# Display-KeyboardModule.net
KiCad netlist of a schematic drawn in EAGLE
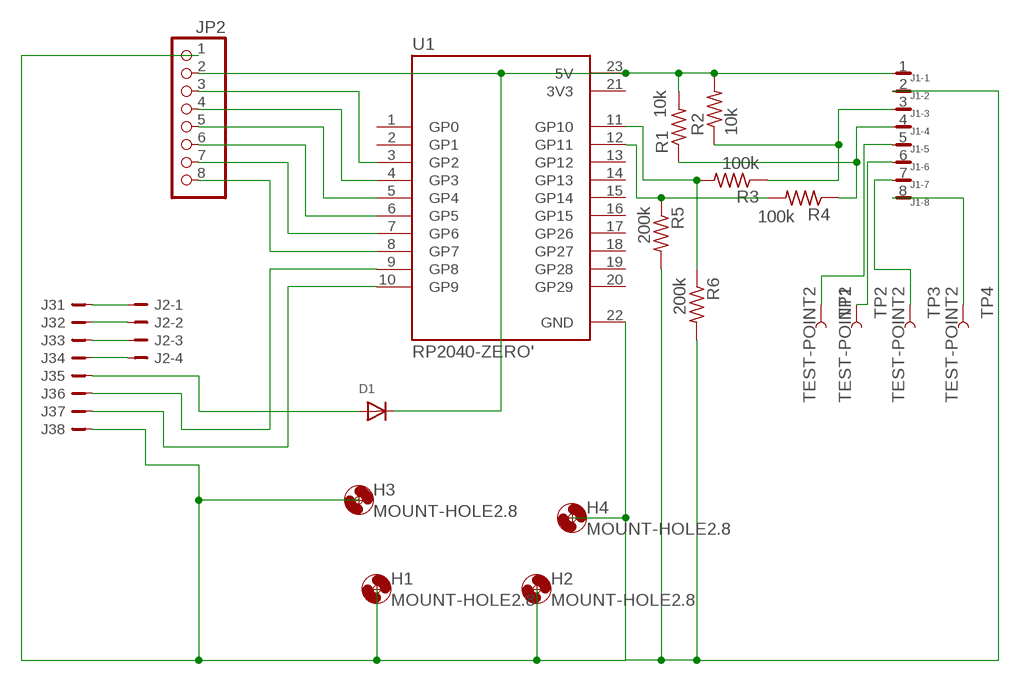
[diagram p0: schematic, sheet 1]

(export (version "E")
  (design (tool "Eeschema 10.0.6"))
  (components
    (comp (ref "D1")
      (value "DIODESMA")
      (footprint "eagle-import:SMADIODE")
      (libsource (lib "eagle-import") (part "DIODESMA"))
    )
    (comp (ref "H1")
      (value "MOUNT-HOLE2.8")
      (footprint "eagle-import:2,8")
      (libsource (lib "eagle-import") (part "MOUNT-HOLE2.8"))
    )
    (comp (ref "H2")
      (value "MOUNT-HOLE2.8")
      (footprint "eagle-import:2,8")
      (libsource (lib "eagle-import") (part "MOUNT-HOLE2.8"))
    )
    (comp (ref "H3")
      (value "MOUNT-HOLE2.8")
      (footprint "eagle-import:2,8")
      (libsource (lib "eagle-import") (part "MOUNT-HOLE2.8"))
    )
    (comp (ref "H4")
      (value "MOUNT-HOLE2.8")
      (footprint "eagle-import:2,8")
      (libsource (lib "eagle-import") (part "MOUNT-HOLE2.8"))
    )
    (comp (ref "J1")
      (value "JST-SH-8_RA")
      (footprint "eagle-import:SM08B-SRSS-TB")
      (fields (field (name "MF") "JST") (field (name "MPN") "SM08B-SRSS-TB"))
      (libsource (lib "eagle-import") (part "JST-SH-8_RA"))
    )
    (comp (ref "J2")
      (value "JST-PH-4_TH-RA")
      (footprint "eagle-import:S4B-PH-KL")
      (fields (field (name "MF") "JST") (field (name "MPN") "S4B-PH-KL"))
      (libsource (lib "eagle-import") (part "JST-PH-4_TH-RA"))
    )
    (comp (ref "J3")
      (value "B8B-PH-K-S")
      (footprint "eagle-import:B8B-PH-K-S")
      (libsource (lib "eagle-import") (part "B8B-PH-K-S"))
    )
    (comp (ref "JP2")
      (value "PINHD-1X8/90")
      (footprint "eagle-import:1X08_90")
      (libsource (lib "eagle-import") (part "PINHD-1X8/90"))
    )
    (comp (ref "R1")
      (value "10k")
      (footprint "eagle-import:R1206")
      (libsource (lib "eagle-import") (part "R-US_R1206"))
    )
    (comp (ref "R2")
      (value "10k")
      (footprint "eagle-import:R1206")
      (libsource (lib "eagle-import") (part "R-US_R1206"))
    )
    (comp (ref "R3")
      (value "100k")
      (footprint "eagle-import:R1206")
      (libsource (lib "eagle-import") (part "R-US_R1206"))
    )
    (comp (ref "R4")
      (value "100k")
      (footprint "eagle-import:R1206")
      (libsource (lib "eagle-import") (part "R-US_R1206"))
    )
    (comp (ref "R5")
      (value "200k")
      (footprint "eagle-import:R1206")
      (libsource (lib "eagle-import") (part "R-US_R1206"))
    )
    (comp (ref "R6")
      (value "200k")
      (footprint "eagle-import:R1206")
      (libsource (lib "eagle-import") (part "R-US_R1206"))
    )
    (comp (ref "TP1")
      (value "TEST-POINT2")
      (footprint "eagle-import:PAD.02X.02")
      (libsource (lib "eagle-import") (part "TEST-POINT2"))
    )
    (comp (ref "TP2")
      (value "TEST-POINT2")
      (footprint "eagle-import:PAD.02X.02")
      (libsource (lib "eagle-import") (part "TEST-POINT2"))
    )
    (comp (ref "TP3")
      (value "TEST-POINT2")
      (footprint "eagle-import:PAD.02X.02")
      (libsource (lib "eagle-import") (part "TEST-POINT2"))
    )
    (comp (ref "TP4")
      (value "TEST-POINT2")
      (footprint "eagle-import:PAD.02X.02")
      (libsource (lib "eagle-import") (part "TEST-POINT2"))
    )
    (comp (ref "U1")
      (value "RP2040-ZERO'")
      (footprint "eagle-import:MODULE_RP2040-ZERO")
      (fields (field (name "MF") "Waveshare Electronics") (field (name "MP") "RP2040-ZERO"))
      (libsource (lib "eagle-import") (part "RP2040-ZERO'"))
    )
  )
  (nets
    (net (code "1") (name "/3V3") (class "Default")
      (node (ref "U1") (pin "21") (pinfunction "3V3_21") (pintype "power_in"))
    )
    (net (code "2") (name "Net-(J1A-P)") (class "Default")
      (node (ref "D1") (pin "C") (pinfunction "C_C") (pintype "passive"))
      (node (ref "J1") (pin "1") (pinfunction "P_1") (pintype "bidirectional"))
      (node (ref "JP2") (pin "2") (pinfunction "2_2") (pintype "passive"))
      (node (ref "R1") (pin "2") (pinfunction "2_2") (pintype "passive"))
      (node (ref "R2") (pin "2") (pinfunction "2_2") (pintype "passive"))
      (node (ref "U1") (pin "23") (pinfunction "5V_23") (pintype "power_in"))
    )
    (net (code "3") (name "Net-(J1B-P)") (class "Default")
      (node (ref "J1") (pin "2") (pinfunction "P_2") (pintype "bidirectional"))
      (node (ref "J3") (pin "8") (pinfunction "1_8") (pintype "passive"))
      (node (ref "JP2") (pin "1") (pinfunction "1_1") (pintype "passive"))
      (node (ref "R5") (pin "2") (pinfunction "2_2") (pintype "passive"))
      (node (ref "R6") (pin "2") (pinfunction "2_2") (pintype "passive"))
      (node (ref "U1") (pin "22") (pinfunction "GND_22") (pintype "power_in"))
    )
    (net (code "4") (name "Net-(J1C-P)") (class "Default")
      (node (ref "J1") (pin "3") (pinfunction "P_3") (pintype "bidirectional"))
      (node (ref "R2") (pin "1") (pinfunction "1_1") (pintype "passive"))
      (node (ref "R3") (pin "1") (pinfunction "1_1") (pintype "passive"))
    )
    (net (code "5") (name "Net-(J1D-P)") (class "Default")
      (node (ref "J1") (pin "4") (pinfunction "P_4") (pintype "bidirectional"))
      (node (ref "R1") (pin "1") (pinfunction "1_1") (pintype "passive"))
      (node (ref "R4") (pin "1") (pinfunction "1_1") (pintype "passive"))
    )
    (net (code "6") (name "Net-(J1E-P)") (class "Default")
      (node (ref "J1") (pin "5") (pinfunction "P_5") (pintype "bidirectional"))
      (node (ref "TP1") (pin "1") (pinfunction "1_1") (pintype "bidirectional"))
    )
    (net (code "7") (name "Net-(J1F-P)") (class "Default")
      (node (ref "J1") (pin "6") (pinfunction "P_6") (pintype "bidirectional"))
      (node (ref "TP2") (pin "1") (pinfunction "1_1") (pintype "bidirectional"))
    )
    (net (code "8") (name "Net-(J1G-P)") (class "Default")
      (node (ref "J1") (pin "7") (pinfunction "P_7") (pintype "bidirectional"))
      (node (ref "TP3") (pin "1") (pinfunction "1_1") (pintype "bidirectional"))
    )
    (net (code "9") (name "Net-(J1H-P)") (class "Default")
      (node (ref "J1") (pin "8") (pinfunction "P_8") (pintype "bidirectional"))
      (node (ref "TP4") (pin "1") (pinfunction "1_1") (pintype "bidirectional"))
    )
    (net (code "10") (name "Net-(J2-Pad1)") (class "Default")
      (node (ref "J2") (pin "1") (pinfunction "1_1") (pintype "passive"))
      (node (ref "J3") (pin "1") (pinfunction "1_1") (pintype "passive"))
    )
    (net (code "11") (name "Net-(J2B-1)") (class "Default")
      (node (ref "J2") (pin "2") (pinfunction "1_2") (pintype "passive"))
      (node (ref "J3") (pin "2") (pinfunction "1_2") (pintype "passive"))
    )
    (net (code "12") (name "Net-(J2C-1)") (class "Default")
      (node (ref "J2") (pin "3") (pinfunction "1_3") (pintype "passive"))
      (node (ref "J3") (pin "3") (pinfunction "1_3") (pintype "passive"))
    )
    (net (code "13") (name "Net-(J2D-1)") (class "Default")
      (node (ref "J2") (pin "4") (pinfunction "1_4") (pintype "passive"))
      (node (ref "J3") (pin "4") (pinfunction "1_4") (pintype "passive"))
    )
    (net (code "14") (name "Net-(J3E-1)") (class "Default")
      (node (ref "D1") (pin "A") (pinfunction "A_A") (pintype "passive"))
      (node (ref "J3") (pin "5") (pinfunction "1_5") (pintype "passive"))
    )
    (net (code "15") (name "Net-(J3F-1)") (class "Default")
      (node (ref "J3") (pin "6") (pinfunction "1_6") (pintype "passive"))
      (node (ref "U1") (pin "9") (pinfunction "GP8_9") (pintype "bidirectional"))
    )
    (net (code "16") (name "Net-(J3G-1)") (class "Default")
      (node (ref "J3") (pin "7") (pinfunction "1_7") (pintype "passive"))
      (node (ref "U1") (pin "10") (pinfunction "GP9_10") (pintype "bidirectional"))
    )
    (net (code "17") (name "Net-(U1-GP2)") (class "Default")
      (node (ref "JP2") (pin "3") (pinfunction "3_3") (pintype "passive"))
      (node (ref "U1") (pin "3") (pinfunction "GP2_3") (pintype "bidirectional"))
    )
    (net (code "18") (name "Net-(U1-GP3)") (class "Default")
      (node (ref "JP2") (pin "4") (pinfunction "4_4") (pintype "passive"))
      (node (ref "U1") (pin "4") (pinfunction "GP3_4") (pintype "bidirectional"))
    )
    (net (code "19") (name "Net-(U1-GP4)") (class "Default")
      (node (ref "JP2") (pin "5") (pinfunction "5_5") (pintype "passive"))
      (node (ref "U1") (pin "5") (pinfunction "GP4_5") (pintype "bidirectional"))
    )
    (net (code "20") (name "Net-(U1-GP5)") (class "Default")
      (node (ref "JP2") (pin "6") (pinfunction "6_6") (pintype "passive"))
      (node (ref "U1") (pin "6") (pinfunction "GP5_6") (pintype "bidirectional"))
    )
    (net (code "21") (name "Net-(U1-GP6)") (class "Default")
      (node (ref "JP2") (pin "7") (pinfunction "7_7") (pintype "passive"))
      (node (ref "U1") (pin "7") (pinfunction "GP6_7") (pintype "bidirectional"))
    )
    (net (code "22") (name "Net-(U1-GP7)") (class "Default")
      (node (ref "JP2") (pin "8") (pinfunction "8_8") (pintype "passive"))
      (node (ref "U1") (pin "8") (pinfunction "GP7_8") (pintype "bidirectional"))
    )
    (net (code "23") (name "Net-(U1-GP10)") (class "Default")
      (node (ref "R3") (pin "2") (pinfunction "2_2") (pintype "passive"))
      (node (ref "R6") (pin "1") (pinfunction "1_1") (pintype "passive"))
      (node (ref "U1") (pin "11") (pinfunction "GP10_11") (pintype "bidirectional"))
    )
    (net (code "24") (name "Net-(U1-GP11)") (class "Default")
      (node (ref "R4") (pin "2") (pinfunction "2_2") (pintype "passive"))
      (node (ref "R5") (pin "1") (pinfunction "1_1") (pintype "passive"))
      (node (ref "U1") (pin "12") (pinfunction "GP11_12") (pintype "bidirectional"))
    )
    (net (code "25") (name "unconnected-(U1-GP0-Pad1)") (class "Default")
      (node (ref "U1") (pin "1") (pinfunction "GP0_1") (pintype "bidirectional"))
    )
    (net (code "26") (name "unconnected-(U1-GP1-Pad2)") (class "Default")
      (node (ref "U1") (pin "2") (pinfunction "GP1_2") (pintype "bidirectional"))
    )
    (net (code "27") (name "unconnected-(U1-GP12-Pad13)") (class "Default")
      (node (ref "U1") (pin "13") (pinfunction "GP12_13") (pintype "bidirectional"))
    )
    (net (code "28") (name "unconnected-(U1-GP13-Pad14)") (class "Default")
      (node (ref "U1") (pin "14") (pinfunction "GP13_14") (pintype "bidirectional"))
    )
    (net (code "29") (name "unconnected-(U1-GP14-Pad15)") (class "Default")
      (node (ref "U1") (pin "15") (pinfunction "GP14_15") (pintype "bidirectional"))
    )
    (net (code "30") (name "unconnected-(U1-GP15-Pad16)") (class "Default")
      (node (ref "U1") (pin "16") (pinfunction "GP15_16") (pintype "bidirectional"))
    )
    (net (code "31") (name "unconnected-(U1-GP26-Pad17)") (class "Default")
      (node (ref "U1") (pin "17") (pinfunction "GP26_17") (pintype "bidirectional"))
    )
    (net (code "32") (name "unconnected-(U1-GP27-Pad18)") (class "Default")
      (node (ref "U1") (pin "18") (pinfunction "GP27_18") (pintype "bidirectional"))
    )
    (net (code "33") (name "unconnected-(U1-GP28-Pad19)") (class "Default")
      (node (ref "U1") (pin "19") (pinfunction "GP28_19") (pintype "bidirectional"))
    )
    (net (code "34") (name "unconnected-(U1-GP29-Pad20)") (class "Default")
      (node (ref "U1") (pin "20") (pinfunction "GP29_20") (pintype "bidirectional"))
    )
  )
)
